# HW1_32.net
KiCad netlist of a schematic drawn in EasyEDA
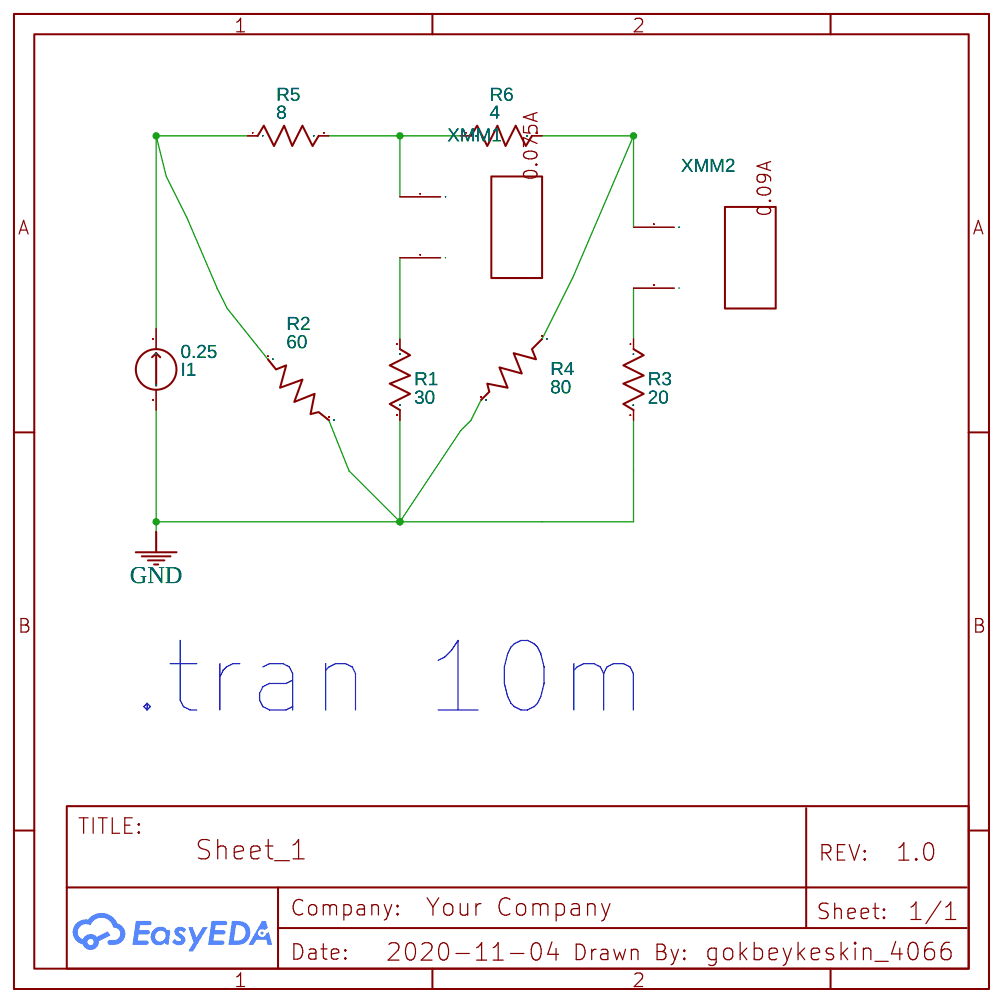
[diagram p0: schematic sheet]

(export (version "E")
  (design (tool "Eeschema 10.0.6"))
  (components
    (comp (ref "I1") (value "0.25") (libsource (lib "") (part "IDC")))
    (comp (ref "R1") (value "30") (libsource (lib "") (part "Resistor_US_1")))
    (comp (ref "R2") (value "60") (libsource (lib "") (part "Resistor_45Degree_US")))
    (comp (ref "R3") (value "20") (libsource (lib "") (part "Resistor_US_1")))
    (comp (ref "R4") (value "80") (libsource (lib "") (part "Resistor_45Degree_US_1")))
    (comp (ref "R5") (value "8") (libsource (lib "") (part "Resistor_US")))
    (comp (ref "R6") (value "4") (libsource (lib "") (part "Resistor_US")))
    (comp (ref "XMM1") (value "Multimeter") (libsource (lib "") (part "MULTIMETER_1")))
    (comp (ref "XMM2") (value "Multimeter") (libsource (lib "") (part "MULTIMETER")))
  )
  (nets
    (net (code "1") (name "GND") (class "Default")
      (node (ref "I1") (pin "1") (pinfunction "1_1") (pintype "unspecified"))
      (node (ref "R1") (pin "2") (pinfunction "2_2") (pintype "unspecified"))
      (node (ref "R2") (pin "2") (pinfunction "2_2") (pintype "unspecified"))
      (node (ref "R3") (pin "2") (pinfunction "2_2") (pintype "unspecified"))
      (node (ref "R4") (pin "2") (pinfunction "2_2") (pintype "unspecified"))
    )
    (net (code "2") (name "Net-(I1-Pad2)") (class "Default")
      (node (ref "I1") (pin "2") (pinfunction "2_2") (pintype "unspecified"))
      (node (ref "R2") (pin "1") (pinfunction "1_1") (pintype "unspecified"))
      (node (ref "R5") (pin "1") (pinfunction "1_1") (pintype "unspecified"))
    )
    (net (code "3") (name "Net-(XMM1-+)") (class "Default")
      (node (ref "R5") (pin "2") (pinfunction "2_2") (pintype "unspecified"))
      (node (ref "R6") (pin "1") (pinfunction "1_1") (pintype "unspecified"))
      (node (ref "XMM1") (pin "1") (pinfunction "+_1") (pintype "unspecified"))
    )
    (net (code "4") (name "Net-(XMM1-I)") (class "Default")
      (node (ref "R1") (pin "1") (pinfunction "1_1") (pintype "unspecified"))
      (node (ref "XMM1") (pin "2") (pinfunction "I_2") (pintype "unspecified"))
    )
    (net (code "5") (name "Net-(XMM2-+)") (class "Default")
      (node (ref "R4") (pin "1") (pinfunction "1_1") (pintype "unspecified"))
      (node (ref "R6") (pin "2") (pinfunction "2_2") (pintype "unspecified"))
      (node (ref "XMM2") (pin "1") (pinfunction "+_1") (pintype "unspecified"))
    )
    (net (code "6") (name "Net-(XMM2-I)") (class "Default")
      (node (ref "R3") (pin "1") (pinfunction "1_1") (pintype "unspecified"))
      (node (ref "XMM2") (pin "2") (pinfunction "I_2") (pintype "unspecified"))
    )
  )
)
